# Attenuator.net
KiCad netlist of a schematic drawn in Altium Designer
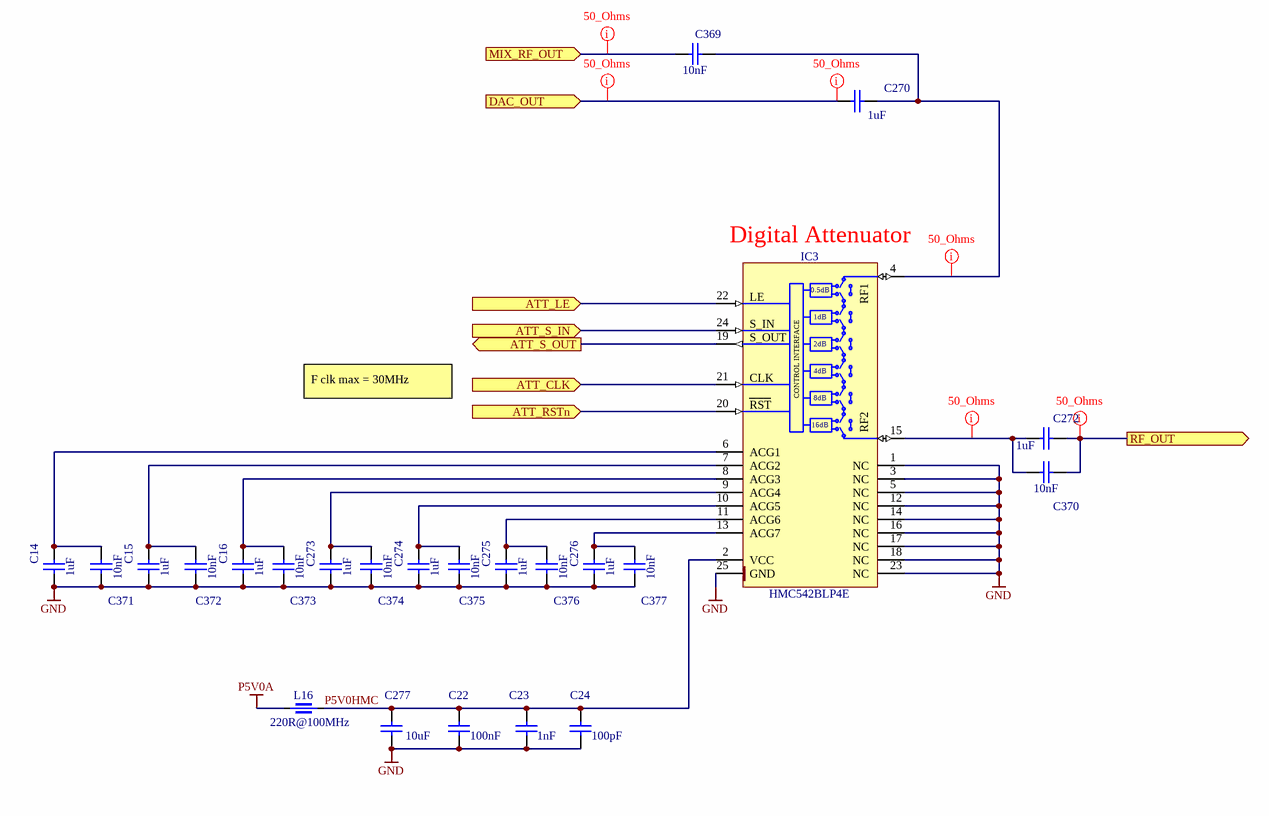
[diagram p0: Attenuator.SchDoc]

(export (version "E")
  (design (tool "Eeschema 10.0.6"))
  (components
    (comp (ref "C14")
      (value "1uF")
      (footprint "CAPC1005X55N")
      (description "Non-polarised capacitor")
      (fields
        (field (name "PART NUMBER") "CC0402_1UF_16V_10%_X5R")
        (field (name "VOLTAGE") "16V")
        (field (name "AUTHOR") "CERN DEM JLC")
      )
      (libsource (lib "Capacitors") (part "Capacitor - non polarized"))
    )
    (comp (ref "C15")
      (value "1uF")
      (footprint "CAPC1005X55N")
      (description "Non-polarised capacitor")
      (fields
        (field (name "PART NUMBER") "CC0402_1UF_16V_10%_X5R")
        (field (name "VOLTAGE") "16V")
        (field (name "AUTHOR") "CERN DEM JLC")
      )
      (libsource (lib "Capacitors") (part "Capacitor - non polarized"))
    )
    (comp (ref "C16")
      (value "1uF")
      (footprint "CAPC1005X55N")
      (description "Non-polarised capacitor")
      (fields
        (field (name "PART NUMBER") "CC0402_1UF_16V_10%_X5R")
        (field (name "VOLTAGE") "16V")
        (field (name "AUTHOR") "CERN DEM JLC")
      )
      (libsource (lib "Capacitors") (part "Capacitor - non polarized"))
    )
    (comp (ref "C22")
      (value "100nF")
      (footprint "CAPC1005X55N")
      (description "Non-polarised capacitor")
      (fields
        (field (name "PART NUMBER") "CC0402_100NF_16V_10%_X7R")
        (field (name "VOLTAGE") "16V")
        (field (name "AUTHOR") "CERN DEM JLC")
      )
      (libsource (lib "Capacitors") (part "Capacitor - non polarized"))
    )
    (comp (ref "C23")
      (value "1nF")
      (footprint "CAPC1005X55N")
      (description "Non-polarised capacitor")
      (fields
        (field (name "PART NUMBER") "CC0402_1NF_50V_10%_X7R")
        (field (name "VOLTAGE") "50V")
        (field (name "AUTHOR") "CERN DEM JLC")
      )
      (libsource (lib "Capacitors") (part "Capacitor - non polarized"))
    )
    (comp (ref "C24")
      (value "100pF")
      (footprint "CAPC1005X55N")
      (description "Non-polarised capacitor")
      (fields
        (field (name "PART NUMBER") "CC0402_100PF_50V_5%_C0G")
        (field (name "VOLTAGE") "50V")
        (field (name "AUTHOR") "CERN DEM JLC")
      )
      (libsource (lib "Capacitors") (part "Capacitor - non polarized"))
    )
    (comp (ref "C270")
      (value "1uF")
      (footprint "CAPC1005X55N")
      (description "Non-polarised capacitor")
      (fields
        (field (name "PART NUMBER") "CC0402_1UF_16V_10%_X5R")
        (field (name "VOLTAGE") "16V")
        (field (name "AUTHOR") "CERN DEM JLC")
      )
      (libsource (lib "Capacitors") (part "Capacitor - non polarized"))
    )
    (comp (ref "C272")
      (value "1uF")
      (footprint "CAPC1005X55N")
      (description "Non-polarised capacitor")
      (fields
        (field (name "PART NUMBER") "CC0402_1UF_16V_10%_X5R")
        (field (name "VOLTAGE") "16V")
        (field (name "AUTHOR") "CERN DEM JLC")
      )
      (libsource (lib "Capacitors") (part "Capacitor - non polarized"))
    )
    (comp (ref "C273")
      (value "1uF")
      (footprint "CAPC1005X55N")
      (description "Non-polarised capacitor")
      (fields
        (field (name "PART NUMBER") "CC0402_1UF_16V_10%_X5R")
        (field (name "VOLTAGE") "16V")
        (field (name "AUTHOR") "CERN DEM JLC")
      )
      (libsource (lib "Capacitors") (part "Capacitor - non polarized"))
    )
    (comp (ref "C274")
      (value "1uF")
      (footprint "CAPC1005X55N")
      (description "Non-polarised capacitor")
      (fields
        (field (name "PART NUMBER") "CC0402_1UF_16V_10%_X5R")
        (field (name "VOLTAGE") "16V")
        (field (name "AUTHOR") "CERN DEM JLC")
      )
      (libsource (lib "Capacitors") (part "Capacitor - non polarized"))
    )
    (comp (ref "C275")
      (value "1uF")
      (footprint "CAPC1005X55N")
      (description "Non-polarised capacitor")
      (fields
        (field (name "PART NUMBER") "CC0402_1UF_16V_10%_X5R")
        (field (name "VOLTAGE") "16V")
        (field (name "AUTHOR") "CERN DEM JLC")
      )
      (libsource (lib "Capacitors") (part "Capacitor - non polarized"))
    )
    (comp (ref "C276")
      (value "1uF")
      (footprint "CAPC1005X55N")
      (description "Non-polarised capacitor")
      (fields
        (field (name "PART NUMBER") "CC0402_1UF_16V_10%_X5R")
        (field (name "VOLTAGE") "16V")
        (field (name "AUTHOR") "CERN DEM JLC")
      )
      (libsource (lib "Capacitors") (part "Capacitor - non polarized"))
    )
    (comp (ref "C277")
      (value "10uF")
      (footprint "CAPC1608X80N")
      (description "Non-polarised capacitor")
      (fields
        (field (name "PART NUMBER") "CC0603_10UF_16V_20%_X5R")
        (field (name "VOLTAGE") "16V")
        (field (name "AUTHOR") "CERN DEM MR")
      )
      (libsource (lib "Capacitors") (part "Capacitor - non polarized"))
    )
    (comp (ref "C369")
      (value "10nF")
      (footprint "CAPC1005X55N")
      (description "Non-polarised capacitor")
      (fields
        (field (name "PART NUMBER") "CC0402_10NF_25V_10%_X7R")
        (field (name "VOLTAGE") "25V")
        (field (name "AUTHOR") "CERN DEM JLC")
      )
      (libsource (lib "Capacitors") (part "Capacitor - non polarized"))
    )
    (comp (ref "C370")
      (value "10nF")
      (footprint "CAPC1005X55N")
      (description "Non-polarised capacitor")
      (fields
        (field (name "PART NUMBER") "CC0402_10NF_25V_10%_X7R")
        (field (name "VOLTAGE") "25V")
        (field (name "AUTHOR") "CERN DEM JLC")
      )
      (libsource (lib "Capacitors") (part "Capacitor - non polarized"))
    )
    (comp (ref "C371")
      (value "10nF")
      (footprint "CAPC1005X55N")
      (description "Non-polarised capacitor")
      (fields
        (field (name "PART NUMBER") "CC0402_10NF_25V_10%_X7R")
        (field (name "VOLTAGE") "25V")
        (field (name "AUTHOR") "CERN DEM JLC")
      )
      (libsource (lib "Capacitors") (part "Capacitor - non polarized"))
    )
    (comp (ref "C372")
      (value "10nF")
      (footprint "CAPC1005X55N")
      (description "Non-polarised capacitor")
      (fields
        (field (name "PART NUMBER") "CC0402_10NF_25V_10%_X7R")
        (field (name "VOLTAGE") "25V")
        (field (name "AUTHOR") "CERN DEM JLC")
      )
      (libsource (lib "Capacitors") (part "Capacitor - non polarized"))
    )
    (comp (ref "C373")
      (value "10nF")
      (footprint "CAPC1005X55N")
      (description "Non-polarised capacitor")
      (fields
        (field (name "PART NUMBER") "CC0402_10NF_25V_10%_X7R")
        (field (name "VOLTAGE") "25V")
        (field (name "AUTHOR") "CERN DEM JLC")
      )
      (libsource (lib "Capacitors") (part "Capacitor - non polarized"))
    )
    (comp (ref "C374")
      (value "10nF")
      (footprint "CAPC1005X55N")
      (description "Non-polarised capacitor")
      (fields
        (field (name "PART NUMBER") "CC0402_10NF_25V_10%_X7R")
        (field (name "VOLTAGE") "25V")
        (field (name "AUTHOR") "CERN DEM JLC")
      )
      (libsource (lib "Capacitors") (part "Capacitor - non polarized"))
    )
    (comp (ref "C375")
      (value "10nF")
      (footprint "CAPC1005X55N")
      (description "Non-polarised capacitor")
      (fields
        (field (name "PART NUMBER") "CC0402_10NF_25V_10%_X7R")
        (field (name "VOLTAGE") "25V")
        (field (name "AUTHOR") "CERN DEM JLC")
      )
      (libsource (lib "Capacitors") (part "Capacitor - non polarized"))
    )
    (comp (ref "C376")
      (value "10nF")
      (footprint "CAPC1005X55N")
      (description "Non-polarised capacitor")
      (fields
        (field (name "PART NUMBER") "CC0402_10NF_25V_10%_X7R")
        (field (name "VOLTAGE") "25V")
        (field (name "AUTHOR") "CERN DEM JLC")
      )
      (libsource (lib "Capacitors") (part "Capacitor - non polarized"))
    )
    (comp (ref "C377")
      (value "10nF")
      (footprint "CAPC1005X55N")
      (description "Non-polarised capacitor")
      (fields
        (field (name "PART NUMBER") "CC0402_10NF_25V_10%_X7R")
        (field (name "VOLTAGE") "25V")
        (field (name "AUTHOR") "CERN DEM JLC")
      )
      (libsource (lib "Capacitors") (part "Capacitor - non polarized"))
    )
    (comp (ref "IC3")
      (value "HMC542BLP4E")
      (footprint "QFN50P400X400X100-25N-S295")
      (description "0.5dB LSB GaAs MMIC 6-bit Digital Serial Control Attenuator, DC - 4GHz")
      (fields (field (name "MANUFACTURER") "HITTITE MICROWAVE CORP") (field (name "AUTHOR") "CERN DEM JMW"))
      (libsource (lib "ICs And Semiconductors") (part "HMC542BLP4E"))
    )
    (comp (ref "L16")
      (value "220R@100MHz")
      (footprint "INDC1608X95N")
      (fields
        (field (name "PART NUMBER") "IND0603_MURATA_BLM18SG221TN1")
        (field (name "POWER") "2.5A")
        (field (name "TOLERANCE") "±25%")
        (field (name "AUTHOR") "CERN DEM MR")
      )
      (libsource (lib "Inductors & Transformers") (part "Ferrite Bead"))
    )
  )
  (nets
    (net (code "1") (name "/ATT_CLK") (class "Default")
      (node (ref "IC3") (pin "21") (pinfunction "SHIFT_CLOCK_21") (pintype "input"))
    )
    (net (code "2") (name "/ATT_LE") (class "Default")
      (node (ref "IC3") (pin "22") (pinfunction "LATCH_ENABLE_22") (pintype "input"))
    )
    (net (code "3") (name "/ATT_RSTn") (class "Default")
      (node (ref "IC3") (pin "20") (pinfunction "~{RESET}_20") (pintype "input"))
    )
    (net (code "4") (name "/ATT_S_IN") (class "Default")
      (node (ref "IC3") (pin "24") (pinfunction "SERIAL_INPUT_24") (pintype "input"))
    )
    (net (code "5") (name "/ATT_S_OUT") (class "Default")
      (node (ref "IC3") (pin "19") (pinfunction "SERIAL_OUTPUT_19") (pintype "output"))
    )
    (net (code "6") (name "/DAC_OUT") (class "Default")
      (node (ref "C270") (pin "2") (pinfunction "2_2") (pintype "passive"))
    )
    (net (code "7") (name "/MIX_RF_OUT") (class "Default")
      (node (ref "C369") (pin "1") (pinfunction "1_1") (pintype "passive"))
    )
    (net (code "8") (name "/P5V0HMC") (class "Default")
      (node (ref "C22") (pin "2") (pinfunction "2_2") (pintype "passive"))
      (node (ref "C23") (pin "2") (pinfunction "2_2") (pintype "passive"))
      (node (ref "C24") (pin "2") (pinfunction "2_2") (pintype "passive"))
      (node (ref "C277") (pin "2") (pinfunction "2_2") (pintype "passive"))
      (node (ref "IC3") (pin "2") (pinfunction "VCC_2") (pintype "power_in"))
      (node (ref "L16") (pin "2") (pinfunction "2_2") (pintype "passive"))
    )
    (net (code "9") (name "/RF_OUT") (class "Default")
      (node (ref "C272") (pin "1") (pinfunction "1_1") (pintype "passive"))
      (node (ref "C370") (pin "2") (pinfunction "2_2") (pintype "passive"))
    )
    (net (code "10") (name "GND") (class "Default")
      (node (ref "C14") (pin "1") (pinfunction "1_1") (pintype "passive"))
      (node (ref "C15") (pin "1") (pinfunction "1_1") (pintype "passive"))
      (node (ref "C16") (pin "1") (pinfunction "1_1") (pintype "passive"))
      (node (ref "C22") (pin "1") (pinfunction "1_1") (pintype "passive"))
      (node (ref "C23") (pin "1") (pinfunction "1_1") (pintype "passive"))
      (node (ref "C24") (pin "1") (pinfunction "1_1") (pintype "passive"))
      (node (ref "C273") (pin "1") (pinfunction "1_1") (pintype "passive"))
      (node (ref "C274") (pin "1") (pinfunction "1_1") (pintype "passive"))
      (node (ref "C275") (pin "1") (pinfunction "1_1") (pintype "passive"))
      (node (ref "C276") (pin "1") (pinfunction "1_1") (pintype "passive"))
      (node (ref "C277") (pin "1") (pinfunction "1_1") (pintype "passive"))
      (node (ref "C371") (pin "1") (pinfunction "1_1") (pintype "passive"))
      (node (ref "C372") (pin "1") (pinfunction "1_1") (pintype "passive"))
      (node (ref "C373") (pin "1") (pinfunction "1_1") (pintype "passive"))
      (node (ref "C374") (pin "1") (pinfunction "1_1") (pintype "passive"))
      (node (ref "C375") (pin "1") (pinfunction "1_1") (pintype "passive"))
      (node (ref "C376") (pin "1") (pinfunction "1_1") (pintype "passive"))
      (node (ref "C377") (pin "1") (pinfunction "1_1") (pintype "passive"))
      (node (ref "IC3") (pin "1") (pinfunction "NC_1") (pintype "passive"))
      (node (ref "IC3") (pin "12") (pinfunction "NC_12") (pintype "passive"))
      (node (ref "IC3") (pin "14") (pinfunction "NC_14") (pintype "passive"))
      (node (ref "IC3") (pin "16") (pinfunction "NC_16") (pintype "passive"))
      (node (ref "IC3") (pin "17") (pinfunction "NC_17") (pintype "passive"))
      (node (ref "IC3") (pin "18") (pinfunction "NC_18") (pintype "passive"))
      (node (ref "IC3") (pin "23") (pinfunction "NC_23") (pintype "passive"))
      (node (ref "IC3") (pin "25") (pinfunction "GND_25") (pintype "power_in"))
      (node (ref "IC3") (pin "3") (pinfunction "NC_3") (pintype "passive"))
      (node (ref "IC3") (pin "5") (pinfunction "NC_5") (pintype "passive"))
    )
    (net (code "11") (name "Net-(IC3-ACG1)") (class "Default")
      (node (ref "C14") (pin "2") (pinfunction "2_2") (pintype "passive"))
      (node (ref "C371") (pin "2") (pinfunction "2_2") (pintype "passive"))
      (node (ref "IC3") (pin "6") (pinfunction "ACG1_6") (pintype "passive"))
    )
    (net (code "12") (name "Net-(IC3-ACG2)") (class "Default")
      (node (ref "C15") (pin "2") (pinfunction "2_2") (pintype "passive"))
      (node (ref "C372") (pin "2") (pinfunction "2_2") (pintype "passive"))
      (node (ref "IC3") (pin "7") (pinfunction "ACG2_7") (pintype "passive"))
    )
    (net (code "13") (name "Net-(IC3-ACG3)") (class "Default")
      (node (ref "C16") (pin "2") (pinfunction "2_2") (pintype "passive"))
      (node (ref "C373") (pin "2") (pinfunction "2_2") (pintype "passive"))
      (node (ref "IC3") (pin "8") (pinfunction "ACG3_8") (pintype "passive"))
    )
    (net (code "14") (name "Net-(IC3-ACG4)") (class "Default")
      (node (ref "C273") (pin "2") (pinfunction "2_2") (pintype "passive"))
      (node (ref "C374") (pin "2") (pinfunction "2_2") (pintype "passive"))
      (node (ref "IC3") (pin "9") (pinfunction "ACG4_9") (pintype "passive"))
    )
    (net (code "15") (name "Net-(IC3-ACG5)") (class "Default")
      (node (ref "C274") (pin "2") (pinfunction "2_2") (pintype "passive"))
      (node (ref "C375") (pin "2") (pinfunction "2_2") (pintype "passive"))
      (node (ref "IC3") (pin "10") (pinfunction "ACG5_10") (pintype "passive"))
    )
    (net (code "16") (name "Net-(IC3-ACG6)") (class "Default")
      (node (ref "C275") (pin "2") (pinfunction "2_2") (pintype "passive"))
      (node (ref "C376") (pin "2") (pinfunction "2_2") (pintype "passive"))
      (node (ref "IC3") (pin "11") (pinfunction "ACG6_11") (pintype "passive"))
    )
    (net (code "17") (name "Net-(IC3-ACG7)") (class "Default")
      (node (ref "C276") (pin "2") (pinfunction "2_2") (pintype "passive"))
      (node (ref "C377") (pin "2") (pinfunction "2_2") (pintype "passive"))
      (node (ref "IC3") (pin "13") (pinfunction "ACG7_13") (pintype "passive"))
    )
    (net (code "18") (name "Net-(IC3-RF1)") (class "Default")
      (node (ref "C270") (pin "1") (pinfunction "1_1") (pintype "passive"))
      (node (ref "C369") (pin "2") (pinfunction "2_2") (pintype "passive"))
      (node (ref "IC3") (pin "4") (pinfunction "RF1_4") (pintype "bidirectional"))
    )
    (net (code "19") (name "Net-(IC3-RF2)") (class "Default")
      (node (ref "C272") (pin "2") (pinfunction "2_2") (pintype "passive"))
      (node (ref "C370") (pin "1") (pinfunction "1_1") (pintype "passive"))
      (node (ref "IC3") (pin "15") (pinfunction "RF2_15") (pintype "bidirectional"))
    )
    (net (code "20") (name "P5V0A") (class "Default")
      (node (ref "L16") (pin "1") (pinfunction "1_1") (pintype "passive"))
    )
  )
)
